# Harvester70.net
KiCad netlist of a schematic drawn in EAGLE
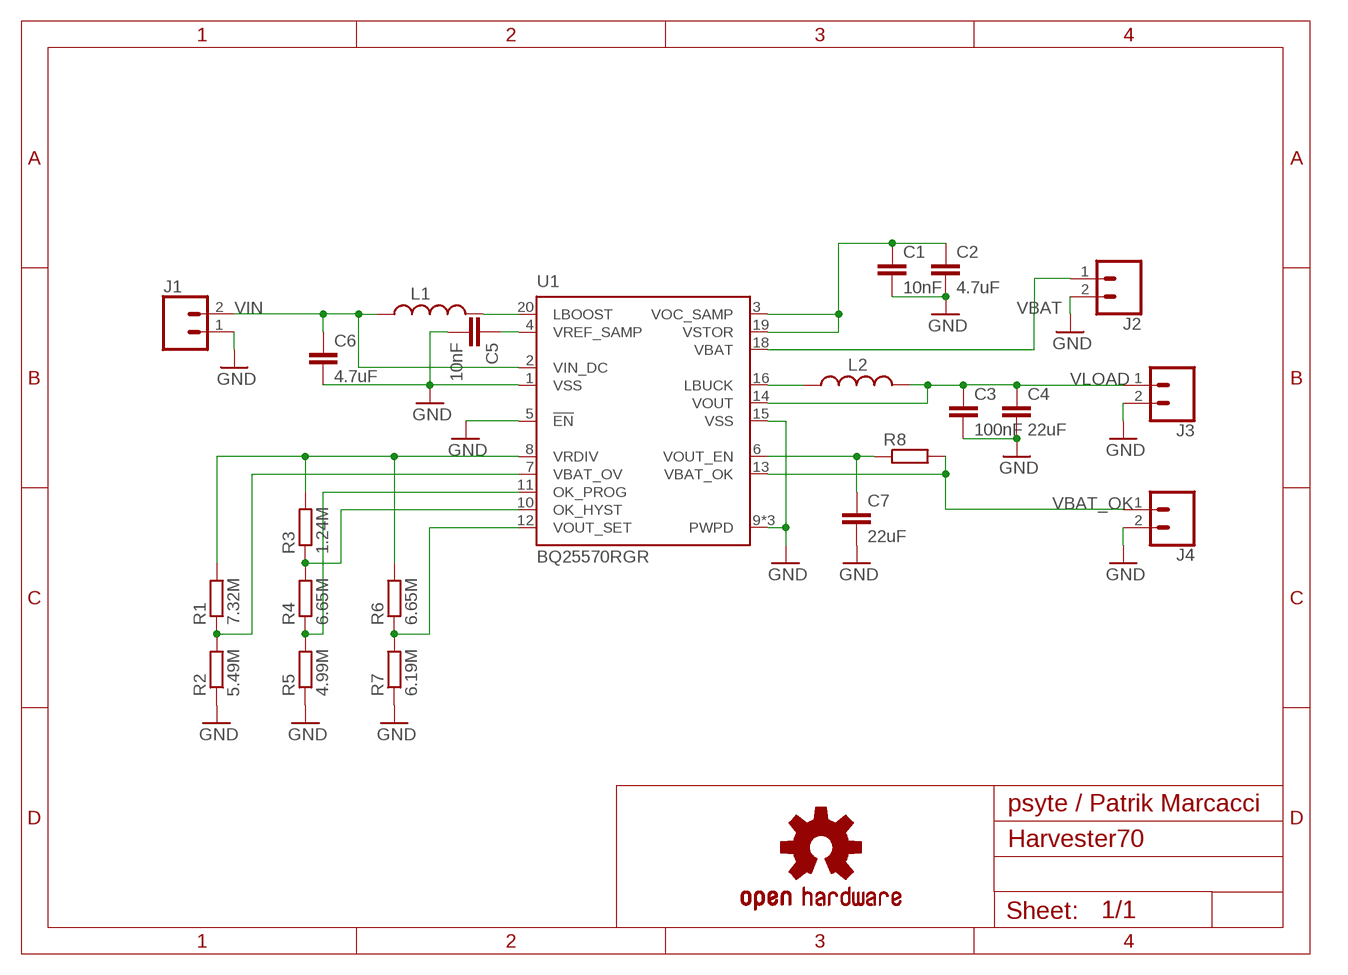
[diagram p0: schematic, sheet 1]

(export (version "E")
  (design (tool "Eeschema 10.0.6"))
  (components
    (comp (ref "C1")
      (value "10nF")
      (footprint "eagle-import:C0603K")
      (libsource (lib "eagle-import") (part "C-EUC0603K"))
    )
    (comp (ref "C2")
      (value "4.7uF")
      (footprint "eagle-import:C0603K")
      (libsource (lib "eagle-import") (part "C-EUC0603K"))
    )
    (comp (ref "C3")
      (value "100nF")
      (footprint "eagle-import:C0603K")
      (libsource (lib "eagle-import") (part "C-EUC0603K"))
    )
    (comp (ref "C4")
      (value "22uF")
      (footprint "eagle-import:C0603K")
      (libsource (lib "eagle-import") (part "C-EUC0603K"))
    )
    (comp (ref "C5")
      (value "10nF")
      (footprint "eagle-import:C0603K")
      (libsource (lib "eagle-import") (part "C-EUC0603K"))
    )
    (comp (ref "C6")
      (value "4.7uF")
      (footprint "eagle-import:C0603K")
      (libsource (lib "eagle-import") (part "C-EUC0603K"))
    )
    (comp (ref "C7")
      (value "22uF")
      (footprint "eagle-import:C0603K")
      (libsource (lib "eagle-import") (part "C-EUC0603K"))
    )
    (comp (ref "J1")
      (value "CONN_02")
      (footprint "eagle-import:1X02")
      (libsource (lib "eagle-import") (part "CONN_02"))
    )
    (comp (ref "J2")
      (value "CONN_02")
      (footprint "eagle-import:1X02")
      (libsource (lib "eagle-import") (part "CONN_02"))
    )
    (comp (ref "J3")
      (value "CONN_02")
      (footprint "eagle-import:1X02")
      (libsource (lib "eagle-import") (part "CONN_02"))
    )
    (comp (ref "J4")
      (value "CONN_02")
      (footprint "eagle-import:1X02")
      (libsource (lib "eagle-import") (part "CONN_02"))
    )
    (comp (ref "L1")
      (value "LPS4018-223M")
      (footprint "eagle-import:LPS4018")
      (libsource (lib "eagle-import") (part "COILCRAFT-LPS4018"))
    )
    (comp (ref "L2")
      (value "LPS4018-103M")
      (footprint "eagle-import:LPS4018")
      (libsource (lib "eagle-import") (part "COILCRAFT-LPS4018"))
    )
    (comp (ref "LOGO2")
      (value "OSHW-LOGOS")
      (footprint "eagle-import:OSHW-LOGO-S")
      (libsource (lib "eagle-import") (part "OSHW-LOGOS"))
    )
    (comp (ref "R1")
      (value "7.32M")
      (footprint "eagle-import:R0603")
      (libsource (lib "eagle-import") (part "R-EU_R0603"))
    )
    (comp (ref "R2")
      (value "5.49M")
      (footprint "eagle-import:R0603")
      (libsource (lib "eagle-import") (part "R-EU_R0603"))
    )
    (comp (ref "R3")
      (value "1.24M")
      (footprint "eagle-import:R0603")
      (libsource (lib "eagle-import") (part "R-EU_R0603"))
    )
    (comp (ref "R4")
      (value "6.65M")
      (footprint "eagle-import:R0603")
      (libsource (lib "eagle-import") (part "R-EU_R0603"))
    )
    (comp (ref "R5")
      (value "4.99M")
      (footprint "eagle-import:R0603")
      (libsource (lib "eagle-import") (part "R-EU_R0603"))
    )
    (comp (ref "R6")
      (value "6.65M")
      (footprint "eagle-import:R0603")
      (libsource (lib "eagle-import") (part "R-EU_R0603"))
    )
    (comp (ref "R7")
      (value "6.19M")
      (footprint "eagle-import:R0603")
      (libsource (lib "eagle-import") (part "R-EU_R0603"))
    )
    (comp (ref "R8")
      (value "R-EU_R0603")
      (footprint "eagle-import:R0603")
      (libsource (lib "eagle-import") (part "R-EU_R0603"))
    )
    (comp (ref "U1")
      (value "BQ25570RGR")
      (footprint "eagle-import:RGR_S-PVQFN-N20")
      (libsource (lib "eagle-import") (part "BQ25570RGR"))
    )
  )
  (nets
    (net (code "1") (name "/VBAT") (class "Default")
      (node (ref "J2") (pin "1") (pinfunction "1_1") (pintype "passive"))
      (node (ref "U1") (pin "18") (pinfunction "VBAT_18") (pintype "power_in"))
    )
    (net (code "2") (name "/VBAT_OK") (class "Default")
      (node (ref "J4") (pin "1") (pinfunction "1_1") (pintype "passive"))
      (node (ref "R8") (pin "2") (pinfunction "2_2") (pintype "passive"))
      (node (ref "U1") (pin "13") (pinfunction "VBAT_OK_13") (pintype "output"))
    )
    (net (code "3") (name "/VIN") (class "Default")
      (node (ref "C6") (pin "1") (pinfunction "1_1") (pintype "passive"))
      (node (ref "J1") (pin "2") (pinfunction "2_2") (pintype "passive"))
      (node (ref "L1") (pin "1") (pinfunction "1_1") (pintype "passive"))
      (node (ref "U1") (pin "2") (pinfunction "VIN_DC_2") (pintype "input"))
    )
    (net (code "4") (name "/VLOAD") (class "Default")
      (node (ref "C3") (pin "1") (pinfunction "1_1") (pintype "passive"))
      (node (ref "C4") (pin "1") (pinfunction "1_1") (pintype "passive"))
      (node (ref "J3") (pin "1") (pinfunction "1_1") (pintype "passive"))
      (node (ref "L2") (pin "2") (pinfunction "2_2") (pintype "passive"))
      (node (ref "U1") (pin "14") (pinfunction "VOUT_14") (pintype "power_in"))
    )
    (net (code "5") (name "GND") (class "Default")
      (node (ref "C1") (pin "2") (pinfunction "2_2") (pintype "passive"))
      (node (ref "C2") (pin "2") (pinfunction "2_2") (pintype "passive"))
      (node (ref "C3") (pin "2") (pinfunction "2_2") (pintype "passive"))
      (node (ref "C4") (pin "2") (pinfunction "2_2") (pintype "passive"))
      (node (ref "C5") (pin "2") (pinfunction "2_2") (pintype "passive"))
      (node (ref "C6") (pin "2") (pinfunction "2_2") (pintype "passive"))
      (node (ref "C7") (pin "2") (pinfunction "2_2") (pintype "passive"))
      (node (ref "J1") (pin "1") (pinfunction "1_1") (pintype "passive"))
      (node (ref "J2") (pin "2") (pinfunction "2_2") (pintype "passive"))
      (node (ref "J3") (pin "2") (pinfunction "2_2") (pintype "passive"))
      (node (ref "J4") (pin "2") (pinfunction "2_2") (pintype "passive"))
      (node (ref "R2") (pin "1") (pinfunction "1_1") (pintype "passive"))
      (node (ref "R5") (pin "1") (pinfunction "1_1") (pintype "passive"))
      (node (ref "R7") (pin "1") (pinfunction "1_1") (pintype "passive"))
      (node (ref "U1") (pin "1") (pinfunction "VSS_1") (pintype "power_in"))
      (node (ref "U1") (pin "15") (pinfunction "VSS_15") (pintype "power_in"))
      (node (ref "U1") (pin "17") (pinfunction "PWPD_17") (pintype "power_in"))
      (node (ref "U1") (pin "5") (pinfunction "~{EN}_5") (pintype "input"))
      (node (ref "U1") (pin "9") (pinfunction "PWPD_9") (pintype "power_in"))
      (node (ref "U1") (pin "EXP") (pinfunction "PWPD_EXP") (pintype "power_in"))
    )
    (net (code "6") (name "Net-(U1-LBOOST)") (class "Default")
      (node (ref "L1") (pin "2") (pinfunction "2_2") (pintype "passive"))
      (node (ref "U1") (pin "20") (pinfunction "LBOOST_20") (pintype "passive"))
    )
    (net (code "7") (name "Net-(U1-LBUCK)") (class "Default")
      (node (ref "L2") (pin "1") (pinfunction "1_1") (pintype "passive"))
      (node (ref "U1") (pin "16") (pinfunction "LBUCK_16") (pintype "passive"))
    )
    (net (code "8") (name "Net-(U1-OK_HYST)") (class "Default")
      (node (ref "R3") (pin "1") (pinfunction "1_1") (pintype "passive"))
      (node (ref "R4") (pin "2") (pinfunction "2_2") (pintype "passive"))
      (node (ref "U1") (pin "10") (pinfunction "OK_HYST_10") (pintype "input"))
    )
    (net (code "9") (name "Net-(U1-OK_PROG)") (class "Default")
      (node (ref "R4") (pin "1") (pinfunction "1_1") (pintype "passive"))
      (node (ref "R5") (pin "2") (pinfunction "2_2") (pintype "passive"))
      (node (ref "U1") (pin "11") (pinfunction "OK_PROG_11") (pintype "input"))
    )
    (net (code "10") (name "Net-(U1-VBAT_OV)") (class "Default")
      (node (ref "R1") (pin "1") (pinfunction "1_1") (pintype "passive"))
      (node (ref "R2") (pin "2") (pinfunction "2_2") (pintype "passive"))
      (node (ref "U1") (pin "7") (pinfunction "VBAT_OV_7") (pintype "input"))
    )
    (net (code "11") (name "Net-(U1-VOC_SAMP)") (class "Default")
      (node (ref "C1") (pin "1") (pinfunction "1_1") (pintype "passive"))
      (node (ref "C2") (pin "1") (pinfunction "1_1") (pintype "passive"))
      (node (ref "U1") (pin "19") (pinfunction "VSTOR_19") (pintype "power_in"))
      (node (ref "U1") (pin "3") (pinfunction "VOC_SAMP_3") (pintype "input"))
    )
    (net (code "12") (name "Net-(U1-VOUT_EN)") (class "Default")
      (node (ref "C7") (pin "1") (pinfunction "1_1") (pintype "passive"))
      (node (ref "R8") (pin "1") (pinfunction "1_1") (pintype "passive"))
      (node (ref "U1") (pin "6") (pinfunction "VOUT_EN_6") (pintype "input"))
    )
    (net (code "13") (name "Net-(U1-VOUT_SET)") (class "Default")
      (node (ref "R6") (pin "1") (pinfunction "1_1") (pintype "passive"))
      (node (ref "R7") (pin "2") (pinfunction "2_2") (pintype "passive"))
      (node (ref "U1") (pin "12") (pinfunction "VOUT_SET_12") (pintype "input"))
    )
    (net (code "14") (name "Net-(U1-VRDIV)") (class "Default")
      (node (ref "R1") (pin "2") (pinfunction "2_2") (pintype "passive"))
      (node (ref "R3") (pin "2") (pinfunction "2_2") (pintype "passive"))
      (node (ref "R6") (pin "2") (pinfunction "2_2") (pintype "passive"))
      (node (ref "U1") (pin "8") (pinfunction "VRDIV_8") (pintype "power_in"))
    )
    (net (code "15") (name "Net-(U1-VREF_SAMP)") (class "Default")
      (node (ref "C5") (pin "1") (pinfunction "1_1") (pintype "passive"))
      (node (ref "U1") (pin "4") (pinfunction "VREF_SAMP_4") (pintype "input"))
    )
  )
)
